# mp28164-buck-boost-flashlight-driver-tes.net
KiCad netlist of a schematic drawn in EAGLE
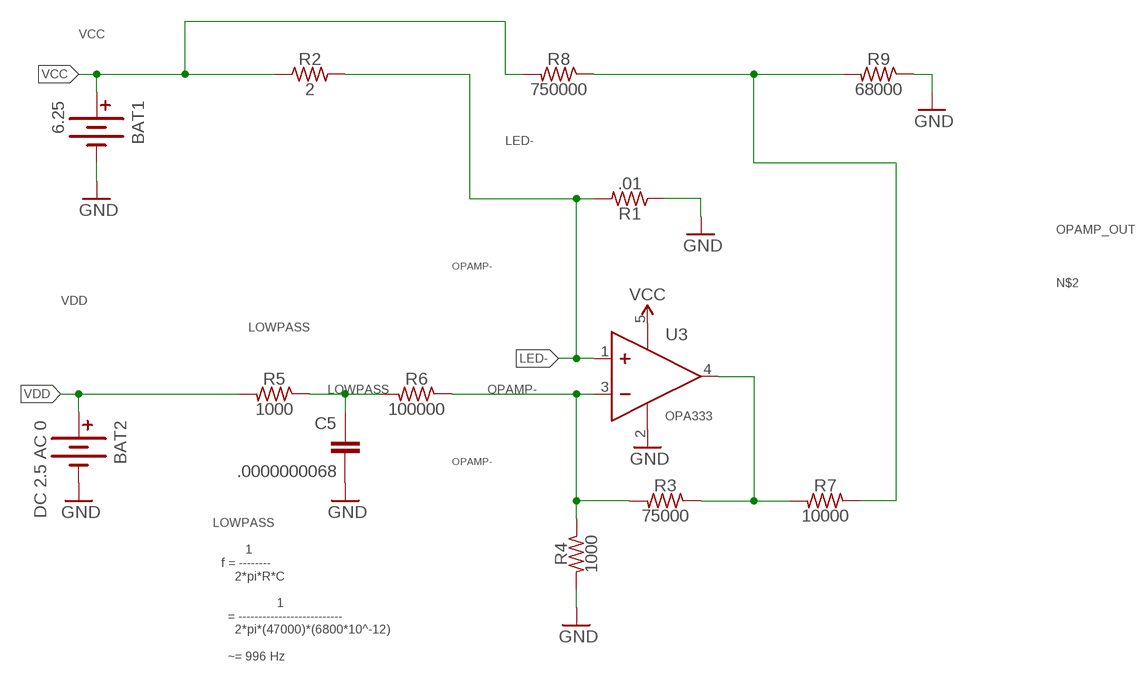
[diagram p0: schematic, sheet 1]

(export (version "E")
  (design (tool "Eeschema 10.0.6"))
  (components
    (comp (ref "BAT1")
      (value "6.25")
      (footprint "eagle-import:BATTCON_9V")
      (fields (field (name "SPICEPREFIX") "V"))
      (libsource (lib "eagle-import") (part "BATTERY9V"))
    )
    (comp (ref "BAT2")
      (value "DC 2.5 AC 0")
      (footprint "eagle-import:BATTCON_9V")
      (fields (field (name "SPICEPREFIX") "V"))
      (libsource (lib "eagle-import") (part "BATTERY9V"))
    )
    (comp (ref "C5")
      (value ".0000000068")
      (footprint "eagle-import:C0402")
      (fields (field (name "SPICEPREFIX") "C"))
      (libsource (lib "eagle-import") (part "CAPACITOR-CERAMICC0402"))
    )
    (comp (ref "R1")
      (value ".01")
      (footprint "eagle-import:R0805-TIGHTER")
      (fields (field (name "SPICEPREFIX") "R"))
      (libsource (lib "eagle-import") (part "RESISTORR0805-TIGHTER"))
    )
    (comp (ref "R2")
      (value "2")
      (footprint "eagle-import:0204V")
      (fields (field (name "SPICEPREFIX") "R"))
      (libsource (lib "eagle-import") (part "RESISTOR0204/2V"))
    )
    (comp (ref "R3")
      (value "75000")
      (footprint "eagle-import:R0402")
      (fields (field (name "SPICEPREFIX") "R"))
      (libsource (lib "eagle-import") (part "RESISTORR0402"))
    )
    (comp (ref "R4")
      (value "1000")
      (footprint "eagle-import:R0402")
      (fields (field (name "SPICEPREFIX") "R"))
      (libsource (lib "eagle-import") (part "RESISTORR0402"))
    )
    (comp (ref "R5")
      (value "1000")
      (footprint "eagle-import:R0402")
      (fields (field (name "SPICEPREFIX") "R"))
      (libsource (lib "eagle-import") (part "RESISTORR0402"))
    )
    (comp (ref "R6")
      (value "100000")
      (footprint "eagle-import:R0402")
      (fields (field (name "SPICEPREFIX") "R"))
      (libsource (lib "eagle-import") (part "RESISTORR0402"))
    )
    (comp (ref "R7")
      (value "10000")
      (footprint "eagle-import:R0402")
      (fields (field (name "SPICEPREFIX") "R"))
      (libsource (lib "eagle-import") (part "RESISTORR0402"))
    )
    (comp (ref "R8")
      (value "750000")
      (footprint "eagle-import:R0402")
      (fields (field (name "SPICEPREFIX") "R"))
      (libsource (lib "eagle-import") (part "RESISTORR0402"))
    )
    (comp (ref "R9")
      (value "68000")
      (footprint "eagle-import:R0402")
      (fields (field (name "SPICEPREFIX") "R"))
      (libsource (lib "eagle-import") (part "RESISTORR0402"))
    )
    (comp (ref "U3")
      (value "OPA333")
      (footprint "eagle-import:SC70")
      (fields (field (name "SPICEMODEL") "OPAMP") (field (name "SPICEPREFIX") "X"))
      (libsource (lib "eagle-import") (part "OPAMPOPA333-SC-70"))
    )
  )
  (nets
    (net (code "1") (name "/LOWPASS") (class "Default")
      (node (ref "C5") (pin "1") (pinfunction "1_1") (pintype "passive"))
      (node (ref "R5") (pin "1") (pinfunction "1_1") (pintype "passive"))
      (node (ref "R6") (pin "2") (pinfunction "2_2") (pintype "passive"))
    )
    (net (code "2") (name "/OPAMP-") (class "Default")
      (node (ref "R3") (pin "2") (pinfunction "2_2") (pintype "passive"))
      (node (ref "R4") (pin "1") (pinfunction "1_1") (pintype "passive"))
      (node (ref "R6") (pin "1") (pinfunction "1_1") (pintype "passive"))
      (node (ref "U3") (pin "3") (pinfunction "IN-_3") (pintype "input"))
    )
    (net (code "3") (name "GND") (class "Default")
      (node (ref "BAT1") (pin "-") (pinfunction "-_-") (pintype "power_in"))
      (node (ref "BAT2") (pin "-") (pinfunction "-_-") (pintype "power_in"))
      (node (ref "C5") (pin "2") (pinfunction "2_2") (pintype "passive"))
      (node (ref "R1") (pin "1") (pinfunction "1_1") (pintype "passive"))
      (node (ref "R4") (pin "2") (pinfunction "2_2") (pintype "passive"))
      (node (ref "R9") (pin "1") (pinfunction "1_1") (pintype "passive"))
      (node (ref "U3") (pin "2") (pinfunction "V-_2") (pintype "power_in"))
    )
    (net (code "4") (name "LED-") (class "Default")
      (node (ref "R1") (pin "2") (pinfunction "2_2") (pintype "passive"))
      (node (ref "R2") (pin "2") (pinfunction "2_2") (pintype "passive"))
      (node (ref "U3") (pin "1") (pinfunction "IN+_1") (pintype "input"))
    )
    (net (code "5") (name "Net-(R7-Pad1)") (class "Default")
      (node (ref "R7") (pin "1") (pinfunction "1_1") (pintype "passive"))
      (node (ref "R8") (pin "1") (pinfunction "1_1") (pintype "passive"))
      (node (ref "R9") (pin "2") (pinfunction "2_2") (pintype "passive"))
    )
    (net (code "6") (name "Net-(U3-OUT)") (class "Default")
      (node (ref "R3") (pin "1") (pinfunction "1_1") (pintype "passive"))
      (node (ref "R7") (pin "2") (pinfunction "2_2") (pintype "passive"))
      (node (ref "U3") (pin "4") (pinfunction "OUT_4") (pintype "output"))
    )
    (net (code "7") (name "VCC") (class "Default")
      (node (ref "BAT1") (pin "+") (pinfunction "+_+") (pintype "power_in"))
      (node (ref "R2") (pin "1") (pinfunction "1_1") (pintype "passive"))
      (node (ref "R8") (pin "2") (pinfunction "2_2") (pintype "passive"))
      (node (ref "U3") (pin "5") (pinfunction "V+_5") (pintype "power_in"))
    )
    (net (code "8") (name "VDD") (class "Default")
      (node (ref "BAT2") (pin "+") (pinfunction "+_+") (pintype "power_in"))
      (node (ref "R5") (pin "2") (pinfunction "2_2") (pintype "passive"))
    )
  )
)
